# MOSFET_Driver_Sheet3.net
KiCad netlist of a schematic drawn in Altium Designer
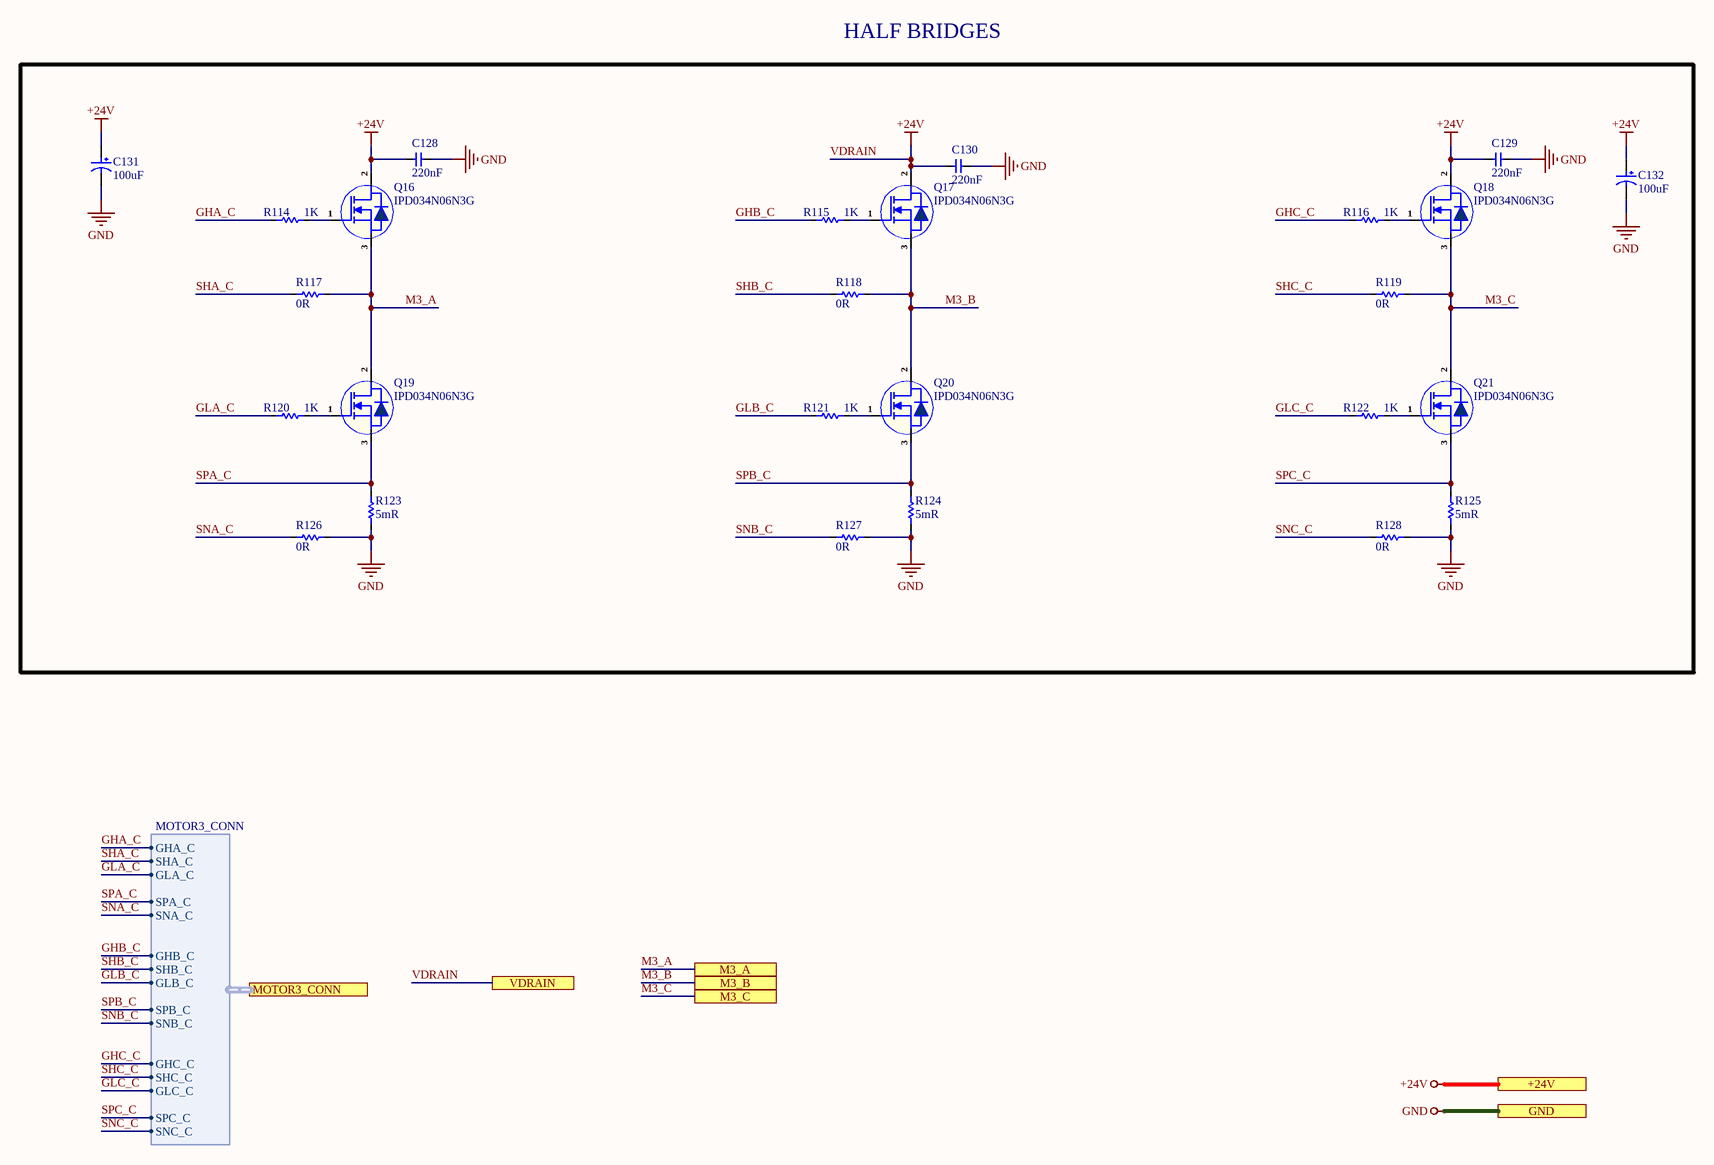
[diagram p0: MOSFET_Driver_Sheet3.SchDoc]

(export (version "E")
  (design (tool "Eeschema 10.0.6"))
  (components
    (comp (ref "C128")
      (value "220nF")
      (footprint "Cap-0805")
      (description "CAP CER 0.22UF 100V X7R 0805")
      (fields
        (field (name "MANUFACTURER") "Kyocera AVX")
        (field (name "MANUFACTURER PART NUMBER") "08051C224K4T2A")
      )
      (libsource (lib "eSpark Libraries") (part "08051C224K4T2A"))
    )
    (comp (ref "C129")
      (value "220nF")
      (footprint "Cap-0805")
      (description "CAP CER 0.22UF 100V X7R 0805")
      (fields
        (field (name "MANUFACTURER") "Kyocera AVX")
        (field (name "MANUFACTURER PART NUMBER") "08051C224K4T2A")
      )
      (libsource (lib "eSpark Libraries") (part "08051C224K4T2A"))
    )
    (comp (ref "C130")
      (value "220nF")
      (footprint "Cap-0805")
      (description "CAP CER 0.22UF 100V X7R 0805")
      (fields
        (field (name "MANUFACTURER") "Kyocera AVX")
        (field (name "MANUFACTURER PART NUMBER") "08051C224K4T2A")
      )
      (libsource (lib "eSpark Libraries") (part "08051C224K4T2A"))
    )
    (comp (ref "C131")
      (value "100uF")
      (footprint "RVT1A101M0605")
      (description "100uF 10V 55mA@120Hz ±20% SMD,D6.3xL5.4mm Aluminum Electrolytic Capacitors - SMD ROHS")
      (fields
        (field (name "MANUFACTURER") "ROQANG")
        (field (name "MANUFACTURER PART NUMBER") "RVT1A101M0605")
      )
      (libsource (lib "eSpark Libraries") (part "RVT1A101M0605"))
    )
    (comp (ref "C132")
      (value "100uF")
      (footprint "RVT1A101M0605")
      (description "100uF 10V 55mA@120Hz ±20% SMD,D6.3xL5.4mm Aluminum Electrolytic Capacitors - SMD ROHS")
      (fields
        (field (name "MANUFACTURER") "ROQANG")
        (field (name "MANUFACTURER PART NUMBER") "RVT1A101M0605")
      )
      (libsource (lib "eSpark Libraries") (part "RVT1A101M0605"))
    )
    (comp (ref "Q16")
      (value "IPD034N06N3G")
      (footprint "TO-252-2L")
      (description "MOSFET N-CH 60V 100A TO252-3")
      (fields (field (name "MANUFACTURER") "Infineon") (field (name "LCSC PART NUMBER") "C94897"))
      (libsource (lib "eSpark Libraries") (part "IPD034N06N3G"))
    )
    (comp (ref "Q17")
      (value "IPD034N06N3G")
      (footprint "TO-252-2L")
      (description "MOSFET N-CH 60V 100A TO252-3")
      (fields (field (name "MANUFACTURER") "Infineon") (field (name "LCSC PART NUMBER") "C94897"))
      (libsource (lib "eSpark Libraries") (part "IPD034N06N3G"))
    )
    (comp (ref "Q18")
      (value "IPD034N06N3G")
      (footprint "TO-252-2L")
      (description "MOSFET N-CH 60V 100A TO252-3")
      (fields (field (name "MANUFACTURER") "Infineon") (field (name "LCSC PART NUMBER") "C94897"))
      (libsource (lib "eSpark Libraries") (part "IPD034N06N3G"))
    )
    (comp (ref "Q19")
      (value "IPD034N06N3G")
      (footprint "TO-252-2L")
      (description "MOSFET N-CH 60V 100A TO252-3")
      (fields (field (name "MANUFACTURER") "Infineon") (field (name "LCSC PART NUMBER") "C94897"))
      (libsource (lib "eSpark Libraries") (part "IPD034N06N3G"))
    )
    (comp (ref "Q20")
      (value "IPD034N06N3G")
      (footprint "TO-252-2L")
      (description "MOSFET N-CH 60V 100A TO252-3")
      (fields (field (name "MANUFACTURER") "Infineon") (field (name "LCSC PART NUMBER") "C94897"))
      (libsource (lib "eSpark Libraries") (part "IPD034N06N3G"))
    )
    (comp (ref "Q21")
      (value "IPD034N06N3G")
      (footprint "TO-252-2L")
      (description "MOSFET N-CH 60V 100A TO252-3")
      (fields (field (name "MANUFACTURER") "Infineon") (field (name "LCSC PART NUMBER") "C94897"))
      (libsource (lib "eSpark Libraries") (part "IPD034N06N3G"))
    )
    (comp (ref "R114")
      (value "1K")
      (footprint "Res-0402")
      (description "RES 1K OHM 1% 1/16W 0402")
      (fields
        (field (name "MANUFACTURER") "Yageo")
        (field (name "MANUFACTURER PART NUMBER") "RC0402FR-071KL")
      )
      (libsource (lib "eSpark Libraries") (part "RC0402FR-071KL"))
    )
    (comp (ref "R115")
      (value "1K")
      (footprint "Res-0402")
      (description "RES 1K OHM 1% 1/16W 0402")
      (fields
        (field (name "MANUFACTURER") "Yageo")
        (field (name "MANUFACTURER PART NUMBER") "RC0402FR-071KL")
      )
      (libsource (lib "eSpark Libraries") (part "RC0402FR-071KL"))
    )
    (comp (ref "R116")
      (value "1K")
      (footprint "Res-0402")
      (description "RES 1K OHM 1% 1/16W 0402")
      (fields
        (field (name "MANUFACTURER") "Yageo")
        (field (name "MANUFACTURER PART NUMBER") "RC0402FR-071KL")
      )
      (libsource (lib "eSpark Libraries") (part "RC0402FR-071KL"))
    )
    (comp (ref "R117")
      (value "0R")
      (footprint "Res-0603")
      (description "RES 0 OHM JUMPER 1/10W 0603")
      (fields
        (field (name "MANUFACTURER") "Yageo")
        (field (name "MANUFACTURER PART NUMBER") "RC0603JR-070RL")
      )
      (libsource (lib "eSpark Libraries") (part "RC0603JR-070RL"))
    )
    (comp (ref "R118")
      (value "0R")
      (footprint "Res-0603")
      (description "RES 0 OHM JUMPER 1/10W 0603")
      (fields
        (field (name "MANUFACTURER") "Yageo")
        (field (name "MANUFACTURER PART NUMBER") "RC0603JR-070RL")
      )
      (libsource (lib "eSpark Libraries") (part "RC0603JR-070RL"))
    )
    (comp (ref "R119")
      (value "0R")
      (footprint "Res-0603")
      (description "RES 0 OHM JUMPER 1/10W 0603")
      (fields
        (field (name "MANUFACTURER") "Yageo")
        (field (name "MANUFACTURER PART NUMBER") "RC0603JR-070RL")
      )
      (libsource (lib "eSpark Libraries") (part "RC0603JR-070RL"))
    )
    (comp (ref "R120")
      (value "1K")
      (footprint "Res-0402")
      (description "RES 1K OHM 1% 1/16W 0402")
      (fields
        (field (name "MANUFACTURER") "Yageo")
        (field (name "MANUFACTURER PART NUMBER") "RC0402FR-071KL")
      )
      (libsource (lib "eSpark Libraries") (part "RC0402FR-071KL"))
    )
    (comp (ref "R121")
      (value "1K")
      (footprint "Res-0402")
      (description "RES 1K OHM 1% 1/16W 0402")
      (fields
        (field (name "MANUFACTURER") "Yageo")
        (field (name "MANUFACTURER PART NUMBER") "RC0402FR-071KL")
      )
      (libsource (lib "eSpark Libraries") (part "RC0402FR-071KL"))
    )
    (comp (ref "R122")
      (value "1K")
      (footprint "Res-0402")
      (description "RES 1K OHM 1% 1/16W 0402")
      (fields
        (field (name "MANUFACTURER") "Yageo")
        (field (name "MANUFACTURER PART NUMBER") "RC0402FR-071KL")
      )
      (libsource (lib "eSpark Libraries") (part "RC0402FR-071KL"))
    )
    (comp (ref "R123")
      (value "5mR")
      (footprint "Res-1206")
      (description "1W 5mΩ ±1% 1206 Current Sense Resistors/Shunt Resistors ROHS")
      (fields
        (field (name "MANUFACTURER") "FORT")
        (field (name "MANUFACTURER PART NUMBER") "CUM1206-15FR005")
      )
      (libsource (lib "eSpark Libraries") (part "CUM1206-15FR005"))
    )
    (comp (ref "R124")
      (value "5mR")
      (footprint "Res-1206")
      (description "1W 5mΩ ±1% 1206 Current Sense Resistors/Shunt Resistors ROHS")
      (fields
        (field (name "MANUFACTURER") "FORT")
        (field (name "MANUFACTURER PART NUMBER") "CUM1206-15FR005")
      )
      (libsource (lib "eSpark Libraries") (part "CUM1206-15FR005"))
    )
    (comp (ref "R125")
      (value "5mR")
      (footprint "Res-1206")
      (description "1W 5mΩ ±1% 1206 Current Sense Resistors/Shunt Resistors ROHS")
      (fields
        (field (name "MANUFACTURER") "FORT")
        (field (name "MANUFACTURER PART NUMBER") "CUM1206-15FR005")
      )
      (libsource (lib "eSpark Libraries") (part "CUM1206-15FR005"))
    )
    (comp (ref "R126")
      (value "0R")
      (footprint "Res-0603")
      (description "RES 0 OHM JUMPER 1/10W 0603")
      (fields
        (field (name "MANUFACTURER") "Yageo")
        (field (name "MANUFACTURER PART NUMBER") "RC0603JR-070RL")
      )
      (libsource (lib "eSpark Libraries") (part "RC0603JR-070RL"))
    )
    (comp (ref "R127")
      (value "0R")
      (footprint "Res-0603")
      (description "RES 0 OHM JUMPER 1/10W 0603")
      (fields
        (field (name "MANUFACTURER") "Yageo")
        (field (name "MANUFACTURER PART NUMBER") "RC0603JR-070RL")
      )
      (libsource (lib "eSpark Libraries") (part "RC0603JR-070RL"))
    )
    (comp (ref "R128")
      (value "0R")
      (footprint "Res-0603")
      (description "RES 0 OHM JUMPER 1/10W 0603")
      (fields
        (field (name "MANUFACTURER") "Yageo")
        (field (name "MANUFACTURER PART NUMBER") "RC0603JR-070RL")
      )
      (libsource (lib "eSpark Libraries") (part "RC0603JR-070RL"))
    )
  )
  (nets
    (net (code "2") (name "+24V") (class "Default")
      (node (ref "C128") (pin "2") (pinfunction "2_2") (pintype "passive"))
      (node (ref "C129") (pin "2") (pinfunction "2_2") (pintype "passive"))
      (node (ref "C130") (pin "2") (pinfunction "2_2") (pintype "passive"))
      (node (ref "C131") (pin "1") (pintype "passive"))
      (node (ref "C132") (pin "1") (pintype "passive"))
      (node (ref "Q16") (pin "2") (pinfunction "D_2") (pintype "passive"))
      (node (ref "Q17") (pin "2") (pinfunction "D_2") (pintype "passive"))
      (node (ref "Q18") (pin "2") (pinfunction "D_2") (pintype "passive"))
    )
    (net (code "3") (name "/GHA_C") (class "Default")
      (node (ref "R114") (pin "1") (pinfunction "1_1") (pintype "passive"))
    )
    (net (code "4") (name "/GHB_C") (class "Default")
      (node (ref "R115") (pin "1") (pinfunction "1_1") (pintype "passive"))
    )
    (net (code "5") (name "/GHC_C") (class "Default")
      (node (ref "R116") (pin "1") (pinfunction "1_1") (pintype "passive"))
    )
    (net (code "6") (name "/GLA_C") (class "Default")
      (node (ref "R120") (pin "1") (pinfunction "1_1") (pintype "passive"))
    )
    (net (code "7") (name "/GLB_C") (class "Default")
      (node (ref "R121") (pin "1") (pinfunction "1_1") (pintype "passive"))
    )
    (net (code "8") (name "/GLC_C") (class "Default")
      (node (ref "R122") (pin "1") (pinfunction "1_1") (pintype "passive"))
    )
    (net (code "9") (name "/M3_A") (class "Default")
      (node (ref "Q16") (pin "3") (pinfunction "S_3") (pintype "passive"))
      (node (ref "Q19") (pin "2") (pinfunction "D_2") (pintype "passive"))
      (node (ref "R117") (pin "1") (pinfunction "1_1") (pintype "passive"))
    )
    (net (code "10") (name "/M3_B") (class "Default")
      (node (ref "Q17") (pin "3") (pinfunction "S_3") (pintype "passive"))
      (node (ref "Q20") (pin "2") (pinfunction "D_2") (pintype "passive"))
      (node (ref "R118") (pin "1") (pinfunction "1_1") (pintype "passive"))
    )
    (net (code "11") (name "/M3_C") (class "Default")
      (node (ref "Q18") (pin "3") (pinfunction "S_3") (pintype "passive"))
      (node (ref "Q21") (pin "2") (pinfunction "D_2") (pintype "passive"))
      (node (ref "R119") (pin "1") (pinfunction "1_1") (pintype "passive"))
    )
    (net (code "12") (name "/SHA_C") (class "Default")
      (node (ref "R117") (pin "2") (pinfunction "2_2") (pintype "passive"))
    )
    (net (code "13") (name "/SHB_C") (class "Default")
      (node (ref "R118") (pin "2") (pinfunction "2_2") (pintype "passive"))
    )
    (net (code "14") (name "/SHC_C") (class "Default")
      (node (ref "R119") (pin "2") (pinfunction "2_2") (pintype "passive"))
    )
    (net (code "15") (name "/SNA_C") (class "Default")
      (node (ref "R126") (pin "2") (pinfunction "2_2") (pintype "passive"))
    )
    (net (code "16") (name "/SNB_C") (class "Default")
      (node (ref "R127") (pin "2") (pinfunction "2_2") (pintype "passive"))
    )
    (net (code "17") (name "/SNC_C") (class "Default")
      (node (ref "R128") (pin "2") (pinfunction "2_2") (pintype "passive"))
    )
    (net (code "18") (name "/SPA_C") (class "Default")
      (node (ref "Q19") (pin "3") (pinfunction "S_3") (pintype "passive"))
      (node (ref "R123") (pin "2") (pinfunction "2_2") (pintype "passive"))
    )
    (net (code "19") (name "/SPB_C") (class "Default")
      (node (ref "Q20") (pin "3") (pinfunction "S_3") (pintype "passive"))
      (node (ref "R124") (pin "2") (pinfunction "2_2") (pintype "passive"))
    )
    (net (code "20") (name "/SPC_C") (class "Default")
      (node (ref "Q21") (pin "3") (pinfunction "S_3") (pintype "passive"))
      (node (ref "R125") (pin "2") (pinfunction "2_2") (pintype "passive"))
    )
    (net (code "22") (name "GND") (class "Default")
      (node (ref "C128") (pin "1") (pinfunction "1_1") (pintype "passive"))
      (node (ref "C129") (pin "1") (pinfunction "1_1") (pintype "passive"))
      (node (ref "C130") (pin "1") (pinfunction "1_1") (pintype "passive"))
      (node (ref "C131") (pin "2") (pintype "passive"))
      (node (ref "C132") (pin "2") (pintype "passive"))
      (node (ref "R123") (pin "1") (pinfunction "1_1") (pintype "passive"))
      (node (ref "R124") (pin "1") (pinfunction "1_1") (pintype "passive"))
      (node (ref "R125") (pin "1") (pinfunction "1_1") (pintype "passive"))
      (node (ref "R126") (pin "1") (pinfunction "1_1") (pintype "passive"))
      (node (ref "R127") (pin "1") (pinfunction "1_1") (pintype "passive"))
      (node (ref "R128") (pin "1") (pinfunction "1_1") (pintype "passive"))
    )
    (net (code "23") (name "Net-(Q16-G)") (class "Default")
      (node (ref "Q16") (pin "1") (pinfunction "G_1") (pintype "passive"))
      (node (ref "R114") (pin "2") (pinfunction "2_2") (pintype "passive"))
    )
    (net (code "24") (name "Net-(Q17-G)") (class "Default")
      (node (ref "Q17") (pin "1") (pinfunction "G_1") (pintype "passive"))
      (node (ref "R115") (pin "2") (pinfunction "2_2") (pintype "passive"))
    )
    (net (code "25") (name "Net-(Q18-G)") (class "Default")
      (node (ref "Q18") (pin "1") (pinfunction "G_1") (pintype "passive"))
      (node (ref "R116") (pin "2") (pinfunction "2_2") (pintype "passive"))
    )
    (net (code "26") (name "Net-(Q19-G)") (class "Default")
      (node (ref "Q19") (pin "1") (pinfunction "G_1") (pintype "passive"))
      (node (ref "R120") (pin "2") (pinfunction "2_2") (pintype "passive"))
    )
    (net (code "27") (name "Net-(Q20-G)") (class "Default")
      (node (ref "Q20") (pin "1") (pinfunction "G_1") (pintype "passive"))
      (node (ref "R121") (pin "2") (pinfunction "2_2") (pintype "passive"))
    )
    (net (code "28") (name "Net-(Q21-G)") (class "Default")
      (node (ref "Q21") (pin "1") (pinfunction "G_1") (pintype "passive"))
      (node (ref "R122") (pin "2") (pinfunction "2_2") (pintype "passive"))
    )
  )
)
